# AUDIO_CODEC_CS4270.net
KiCad netlist of a schematic drawn in Altium Designer
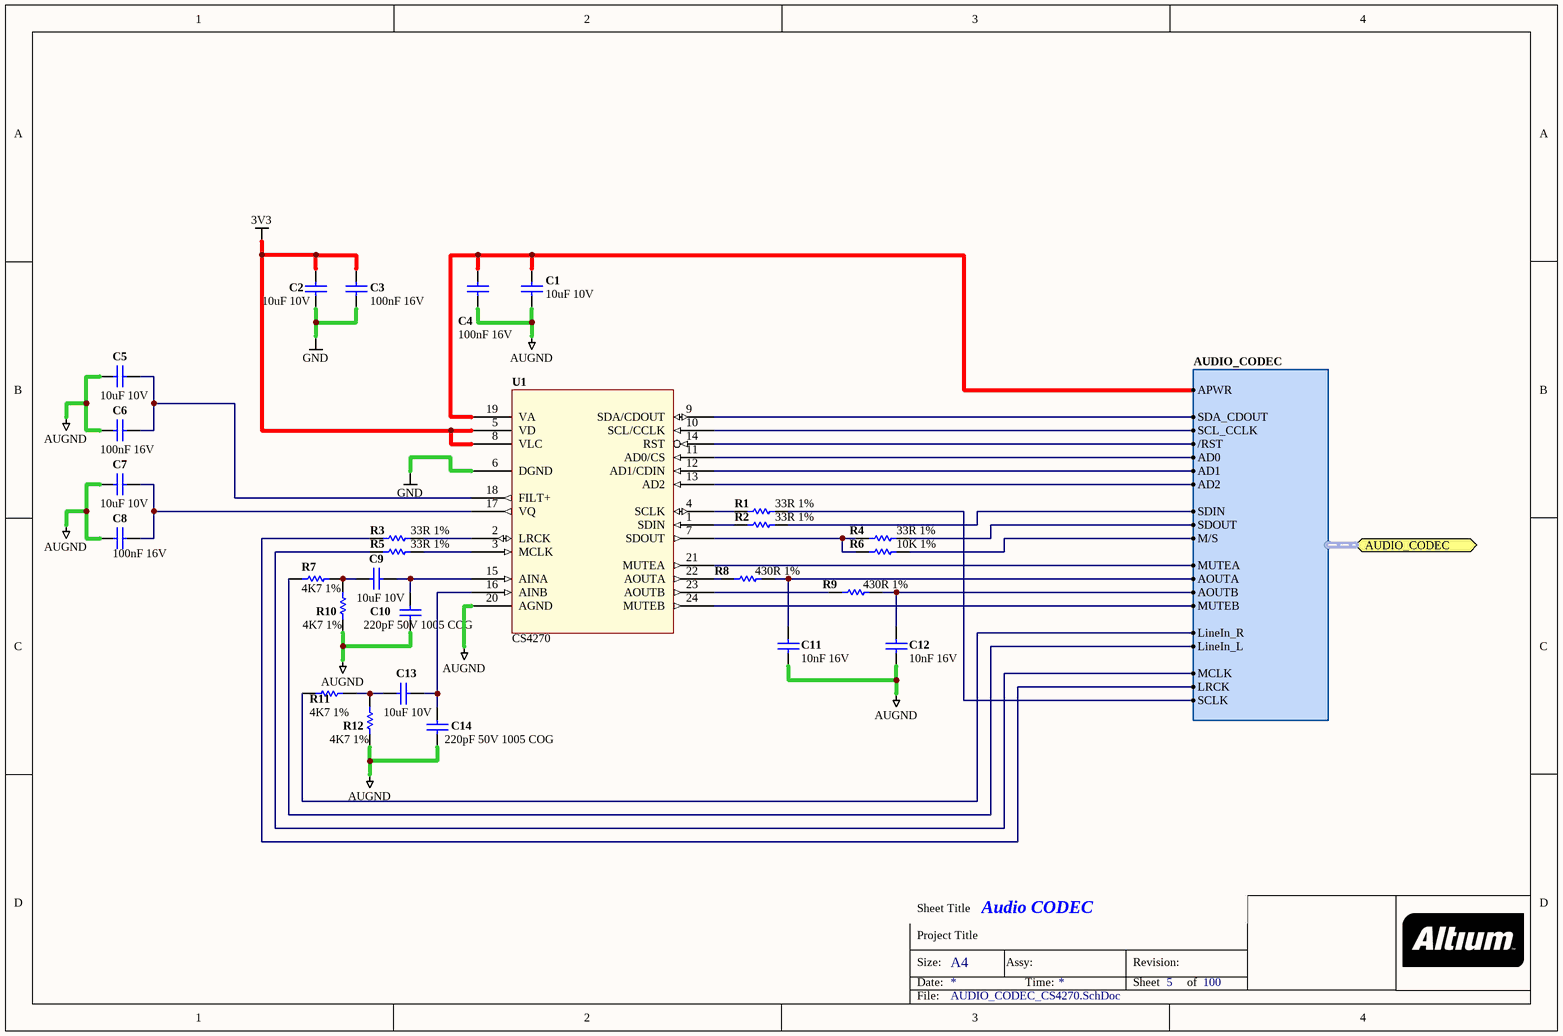
[diagram p0: AUDIO_CODEC_CS4270.SchDoc]

(export (version "E")
  (design (tool "Eeschema 10.0.6"))
  (components
    (comp (ref "C1")
      (value "10uF 10V")
      (footprint "CAPC2012-STAR")
      (description "Capacitor, Ceramic, 10uF 10% 10V 0805 (2012) X5R")
      (fields (field (name "TOLERANCE") "10 %"))
      (libsource (lib "AltiumDesignLibrary") (part "CAP-NP"))
    )
    (comp (ref "C2")
      (value "10uF 10V")
      (footprint "CAPC2012-STAR")
      (description "Capacitor, Ceramic, 10uF 10% 10V 0805 (2012) X5R")
      (fields (field (name "TOLERANCE") "10 %"))
      (libsource (lib "AltiumDesignLibrary") (part "CAP-NP"))
    )
    (comp (ref "C3")
      (value "100nF 16V")
      (footprint "CAPC1005-STAR")
      (description "Capacitor, Ceramic, 100nF 10% 16V 0402 (1005) X7R")
      (fields (field (name "TOLERANCE") "10 %"))
      (libsource (lib "AltiumDesignLibrary") (part "CAP-NP"))
    )
    (comp (ref "C4")
      (value "100nF 16V")
      (footprint "CAPC1005-STAR")
      (description "Capacitor, Ceramic, 100nF 10% 16V 0402 (1005) X7R")
      (fields (field (name "TOLERANCE") "10 %"))
      (libsource (lib "AltiumDesignLibrary") (part "CAP-NP"))
    )
    (comp (ref "C5")
      (value "10uF 10V")
      (footprint "CAPC2012-STAR")
      (description "Capacitor, Ceramic, 10uF 10% 10V 0805 (2012) X5R")
      (fields (field (name "TOLERANCE") "10 %"))
      (libsource (lib "AltiumDesignLibrary") (part "CAP-NP"))
    )
    (comp (ref "C6")
      (value "100nF 16V")
      (footprint "CAPC1005-STAR")
      (description "Capacitor, Ceramic, 100nF 10% 16V 0402 (1005) X7R")
      (fields (field (name "TOLERANCE") "10 %"))
      (libsource (lib "AltiumDesignLibrary") (part "CAP-NP"))
    )
    (comp (ref "C7")
      (value "10uF 10V")
      (footprint "CAPC2012-STAR")
      (description "Capacitor, Ceramic, 10uF 10% 10V 0805 (2012) X5R")
      (fields (field (name "TOLERANCE") "10 %"))
      (libsource (lib "AltiumDesignLibrary") (part "CAP-NP"))
    )
    (comp (ref "C8")
      (value "100nF 16V")
      (footprint "CAPC1005-STAR")
      (description "Capacitor, Ceramic, 100nF 10% 16V 0402 (1005) X7R")
      (fields (field (name "TOLERANCE") "10 %"))
      (libsource (lib "AltiumDesignLibrary") (part "CAP-NP"))
    )
    (comp (ref "C9")
      (value "10uF 10V")
      (footprint "CAPC2012-STAR")
      (description "Capacitor, Ceramic, 10uF 10% 10V 0805 (2012) X5R")
      (fields (field (name "TOLERANCE") "10 %"))
      (libsource (lib "AltiumDesignLibrary") (part "CAP-NP"))
    )
    (comp (ref "C10")
      (value "220pF 50V 1005 COG")
      (footprint "CAPC1005-STAR")
      (description "Capacitor, Ceramic, 220pF 5% 50V 0402 (1005) COG")
      (fields (field (name "TOLERANCE") "5 %"))
      (libsource (lib "AltiumDesignLibrary") (part "CAP-NP"))
    )
    (comp (ref "C11")
      (value "10nF 16V")
      (footprint "CAPC1005-STAR")
      (description "Capacitor, Ceramic, 10nF 10% 16V 0402 (1005) X7R")
      (fields (field (name "TOLERANCE") "10 %"))
      (libsource (lib "AltiumDesignLibrary") (part "CAP-NP"))
    )
    (comp (ref "C12")
      (value "10nF 16V")
      (footprint "CAPC1005-STAR")
      (description "Capacitor, Ceramic, 10nF 10% 16V 0402 (1005) X7R")
      (fields (field (name "TOLERANCE") "10 %"))
      (libsource (lib "AltiumDesignLibrary") (part "CAP-NP"))
    )
    (comp (ref "C13")
      (value "10uF 10V")
      (footprint "CAPC2012-STAR")
      (description "Capacitor, Ceramic, 10uF 10% 10V 0805 (2012) X5R")
      (fields (field (name "TOLERANCE") "10 %"))
      (libsource (lib "AltiumDesignLibrary") (part "CAP-NP"))
    )
    (comp (ref "C14")
      (value "220pF 50V 1005 COG")
      (footprint "CAPC1005-STAR")
      (description "Capacitor, Ceramic, 220pF 5% 50V 0402 (1005) COG")
      (fields (field (name "TOLERANCE") "5 %"))
      (libsource (lib "AltiumDesignLibrary") (part "CAP-NP"))
    )
    (comp (ref "R1")
      (value "33R 1%")
      (footprint "RESC1005-STAR")
      (description "Resistor, 33R 1% 0402 (1005)")
      (fields (field (name "TOLERANCE") "1 %"))
      (libsource (lib "AltiumDesignLibrary") (part "RES"))
    )
    (comp (ref "R2")
      (value "33R 1%")
      (footprint "RESC1005-STAR")
      (description "Resistor, 33R 1% 0402 (1005)")
      (fields (field (name "TOLERANCE") "1 %"))
      (libsource (lib "AltiumDesignLibrary") (part "RES"))
    )
    (comp (ref "R3")
      (value "33R 1%")
      (footprint "RESC1005-STAR")
      (description "Resistor, 33R 1% 0402 (1005)")
      (fields (field (name "TOLERANCE") "1 %"))
      (libsource (lib "AltiumDesignLibrary") (part "RES"))
    )
    (comp (ref "R4")
      (value "33R 1%")
      (footprint "RESC1005-STAR")
      (description "Resistor, 33R 1% 0402 (1005)")
      (fields (field (name "TOLERANCE") "1 %"))
      (libsource (lib "AltiumDesignLibrary") (part "RES"))
    )
    (comp (ref "R5")
      (value "33R 1%")
      (footprint "RESC1005-STAR")
      (description "Resistor, 33R 1% 0402 (1005)")
      (fields (field (name "TOLERANCE") "1 %"))
      (libsource (lib "AltiumDesignLibrary") (part "RES"))
    )
    (comp (ref "R6")
      (value "10K 1%")
      (footprint "RESC1005-STAR")
      (description "Resistor, 10K 1% 0402 (1005)")
      (fields (field (name "TOLERANCE") "1 %"))
      (libsource (lib "AltiumDesignLibrary") (part "RES"))
    )
    (comp (ref "R7")
      (value "4K7 1%")
      (footprint "RESC1005-STAR")
      (description "Resistor, 4K7 1% 0402 (1005)")
      (fields (field (name "TOLERANCE") "1 %"))
      (libsource (lib "AltiumDesignLibrary") (part "RES"))
    )
    (comp (ref "R8")
      (value "430R 1%")
      (footprint "RESC1005-STAR")
      (description "Resistor, 430R 1% 0402 (1005)")
      (fields (field (name "TOLERANCE") "1 %"))
      (libsource (lib "AltiumDesignLibrary") (part "RES"))
    )
    (comp (ref "R9")
      (value "430R 1%")
      (footprint "RESC1005-STAR")
      (description "Resistor, 430R 1% 0402 (1005)")
      (fields (field (name "TOLERANCE") "1 %"))
      (libsource (lib "AltiumDesignLibrary") (part "RES"))
    )
    (comp (ref "R10")
      (value "4K7 1%")
      (footprint "RESC1005-STAR")
      (description "Resistor, 4K7 1% 0402 (1005)")
      (fields (field (name "TOLERANCE") "1 %"))
      (libsource (lib "AltiumDesignLibrary") (part "RES"))
    )
    (comp (ref "R11")
      (value "4K7 1%")
      (footprint "RESC1005-STAR")
      (description "Resistor, 4K7 1% 0402 (1005)")
      (fields (field (name "TOLERANCE") "1 %"))
      (libsource (lib "AltiumDesignLibrary") (part "RES"))
    )
    (comp (ref "R12")
      (value "4K7 1%")
      (footprint "RESC1005-STAR")
      (description "Resistor, 4K7 1% 0402 (1005)")
      (fields (field (name "TOLERANCE") "1 %"))
      (libsource (lib "AltiumDesignLibrary") (part "RES"))
    )
    (comp (ref "U1")
      (value "CS4270")
      (footprint "TSSOP-24")
      (description "CS4270; 24-Bit, 192 kHz Stereo Audio CODEC")
      (libsource (lib "AltiumDesignLibrary") (part "CS4270"))
    )
  )
  (nets
    (net (code "3") (name "3V3") (class "Default")
      (node (ref "C2") (pin "1") (pinfunction "1_1") (pintype "passive"))
      (node (ref "C3") (pin "1") (pinfunction "1_1") (pintype "passive"))
      (node (ref "U1") (pin "5") (pinfunction "VD_5") (pintype "power_in"))
      (node (ref "U1") (pin "8") (pinfunction "VLC_8") (pintype "power_in"))
    )
    (net (code "4") (name "AUGND") (class "Default")
      (node (ref "C1") (pin "2") (pinfunction "2_2") (pintype "passive"))
      (node (ref "C10") (pin "2") (pinfunction "2_2") (pintype "passive"))
      (node (ref "C11") (pin "2") (pinfunction "2_2") (pintype "passive"))
      (node (ref "C12") (pin "2") (pinfunction "2_2") (pintype "passive"))
      (node (ref "C14") (pin "2") (pinfunction "2_2") (pintype "passive"))
      (node (ref "C4") (pin "2") (pinfunction "2_2") (pintype "passive"))
      (node (ref "C5") (pin "2") (pinfunction "2_2") (pintype "passive"))
      (node (ref "C6") (pin "1") (pinfunction "1_1") (pintype "passive"))
      (node (ref "C7") (pin "2") (pinfunction "2_2") (pintype "passive"))
      (node (ref "C8") (pin "2") (pinfunction "2_2") (pintype "passive"))
      (node (ref "R10") (pin "1") (pinfunction "1_1") (pintype "passive"))
      (node (ref "R12") (pin "1") (pinfunction "1_1") (pintype "passive"))
      (node (ref "U1") (pin "20") (pinfunction "AGND_20") (pintype "power_in"))
    )
    (net (code "5") (name "GND") (class "Default")
      (node (ref "C2") (pin "2") (pinfunction "2_2") (pintype "passive"))
      (node (ref "C3") (pin "2") (pinfunction "2_2") (pintype "passive"))
      (node (ref "U1") (pin "6") (pinfunction "DGND_6") (pintype "power_in"))
    )
    (net (code "6") (name "Net-(C9-Pad2)") (class "Default")
      (node (ref "C9") (pin "2") (pinfunction "2_2") (pintype "passive"))
      (node (ref "R10") (pin "2") (pinfunction "2_2") (pintype "passive"))
      (node (ref "R7") (pin "2") (pinfunction "2_2") (pintype "passive"))
    )
    (net (code "7") (name "Net-(C11-Pad1)") (class "Default")
      (node (ref "C11") (pin "1") (pinfunction "1_1") (pintype "passive"))
      (node (ref "R8") (pin "1") (pinfunction "1_1") (pintype "passive"))
    )
    (net (code "8") (name "Net-(C12-Pad1)") (class "Default")
      (node (ref "C12") (pin "1") (pinfunction "1_1") (pintype "passive"))
      (node (ref "R9") (pin "1") (pinfunction "1_1") (pintype "passive"))
    )
    (net (code "9") (name "Net-(C13-Pad2)") (class "Default")
      (node (ref "C13") (pin "2") (pinfunction "2_2") (pintype "passive"))
      (node (ref "R11") (pin "2") (pinfunction "2_2") (pintype "passive"))
      (node (ref "R12") (pin "2") (pinfunction "2_2") (pintype "passive"))
    )
    (net (code "10") (name "Net-(U1-AINA)") (class "Default")
      (node (ref "C10") (pin "1") (pinfunction "1_1") (pintype "passive"))
      (node (ref "C9") (pin "1") (pinfunction "1_1") (pintype "passive"))
      (node (ref "U1") (pin "15") (pinfunction "AINA_15") (pintype "input"))
    )
    (net (code "11") (name "Net-(U1-AINB)") (class "Default")
      (node (ref "C13") (pin "1") (pinfunction "1_1") (pintype "passive"))
      (node (ref "C14") (pin "1") (pinfunction "1_1") (pintype "passive"))
      (node (ref "U1") (pin "16") (pinfunction "AINB_16") (pintype "input"))
    )
    (net (code "12") (name "Net-(U1-AOUTA)") (class "Default")
      (node (ref "R8") (pin "2") (pinfunction "2_2") (pintype "passive"))
      (node (ref "U1") (pin "22") (pinfunction "AOUTA_22") (pintype "output"))
    )
    (net (code "13") (name "Net-(U1-AOUTB)") (class "Default")
      (node (ref "R9") (pin "2") (pinfunction "2_2") (pintype "passive"))
      (node (ref "U1") (pin "23") (pinfunction "AOUTB_23") (pintype "output"))
    )
    (net (code "14") (name "Net-(U1-FILT+)") (class "Default")
      (node (ref "C5") (pin "1") (pinfunction "1_1") (pintype "passive"))
      (node (ref "C6") (pin "2") (pinfunction "2_2") (pintype "passive"))
      (node (ref "U1") (pin "18") (pinfunction "FILT+_18") (pintype "output"))
    )
    (net (code "15") (name "Net-(U1-LRCK)") (class "Default")
      (node (ref "R3") (pin "2") (pinfunction "2_2") (pintype "passive"))
      (node (ref "U1") (pin "2") (pinfunction "LRCK_2") (pintype "bidirectional"))
    )
    (net (code "16") (name "Net-(U1-MCLK)") (class "Default")
      (node (ref "R5") (pin "2") (pinfunction "2_2") (pintype "passive"))
      (node (ref "U1") (pin "3") (pinfunction "MCLK_3") (pintype "input"))
    )
    (net (code "17") (name "Net-(U1-SCLK)") (class "Default")
      (node (ref "R1") (pin "1") (pinfunction "1_1") (pintype "passive"))
      (node (ref "U1") (pin "4") (pinfunction "SCLK_4") (pintype "bidirectional"))
    )
    (net (code "18") (name "Net-(U1-SDIN)") (class "Default")
      (node (ref "R2") (pin "1") (pinfunction "1_1") (pintype "passive"))
      (node (ref "U1") (pin "1") (pinfunction "SDIN_1") (pintype "input"))
    )
    (net (code "19") (name "Net-(U1-SDOUT)") (class "Default")
      (node (ref "R4") (pin "1") (pinfunction "1_1") (pintype "passive"))
      (node (ref "R6") (pin "2") (pinfunction "2_2") (pintype "passive"))
      (node (ref "U1") (pin "7") (pinfunction "SDOUT_7") (pintype "output"))
    )
    (net (code "20") (name "Net-(U1-VA)") (class "Default")
      (node (ref "C1") (pin "1") (pinfunction "1_1") (pintype "passive"))
      (node (ref "C4") (pin "1") (pinfunction "1_1") (pintype "passive"))
      (node (ref "U1") (pin "19") (pinfunction "VA_19") (pintype "power_in"))
    )
    (net (code "21") (name "Net-(U1-VQ)") (class "Default")
      (node (ref "C7") (pin "1") (pinfunction "1_1") (pintype "passive"))
      (node (ref "C8") (pin "1") (pinfunction "1_1") (pintype "passive"))
      (node (ref "U1") (pin "17") (pinfunction "VQ_17") (pintype "output"))
    )
    (net (code "22") (name "unconnected-(R1-Pad2)") (class "Default")
      (node (ref "R1") (pin "2") (pinfunction "2_2") (pintype "passive"))
    )
    (net (code "23") (name "unconnected-(R2-Pad2)") (class "Default")
      (node (ref "R2") (pin "2") (pinfunction "2_2") (pintype "passive"))
    )
    (net (code "24") (name "unconnected-(R3-Pad1)") (class "Default")
      (node (ref "R3") (pin "1") (pinfunction "1_1") (pintype "passive"))
    )
    (net (code "25") (name "unconnected-(R4-Pad2)") (class "Default")
      (node (ref "R4") (pin "2") (pinfunction "2_2") (pintype "passive"))
    )
    (net (code "26") (name "unconnected-(R5-Pad1)") (class "Default")
      (node (ref "R5") (pin "1") (pinfunction "1_1") (pintype "passive"))
    )
    (net (code "27") (name "unconnected-(R6-Pad1)") (class "Default")
      (node (ref "R6") (pin "1") (pinfunction "1_1") (pintype "passive"))
    )
    (net (code "28") (name "unconnected-(R7-Pad1)") (class "Default")
      (node (ref "R7") (pin "1") (pinfunction "1_1") (pintype "passive"))
    )
    (net (code "29") (name "unconnected-(R11-Pad1)") (class "Default")
      (node (ref "R11") (pin "1") (pinfunction "1_1") (pintype "passive"))
    )
    (net (code "30") (name "unconnected-(U1-AD0{slash}CS-Pad11)") (class "Default")
      (node (ref "U1") (pin "11") (pinfunction "AD0/CS_11") (pintype "input"))
    )
    (net (code "31") (name "unconnected-(U1-AD1{slash}CDIN-Pad12)") (class "Default")
      (node (ref "U1") (pin "12") (pinfunction "AD1/CDIN_12") (pintype "input"))
    )
    (net (code "32") (name "unconnected-(U1-AD2-Pad13)") (class "Default")
      (node (ref "U1") (pin "13") (pinfunction "AD2_13") (pintype "input"))
    )
    (net (code "33") (name "unconnected-(U1-MUTEA-Pad21)") (class "Default")
      (node (ref "U1") (pin "21") (pinfunction "MUTEA_21") (pintype "output"))
    )
    (net (code "34") (name "unconnected-(U1-MUTEB-Pad24)") (class "Default")
      (node (ref "U1") (pin "24") (pinfunction "MUTEB_24") (pintype "output"))
    )
    (net (code "35") (name "unconnected-(U1-RST-Pad14)") (class "Default")
      (node (ref "U1") (pin "14") (pinfunction "RST_14") (pintype "input"))
    )
    (net (code "36") (name "unconnected-(U1-SCL{slash}CCLK-Pad10)") (class "Default")
      (node (ref "U1") (pin "10") (pinfunction "SCL/CCLK_10") (pintype "input"))
    )
    (net (code "37") (name "unconnected-(U1-SDA{slash}CDOUT-Pad9)") (class "Default")
      (node (ref "U1") (pin "9") (pinfunction "SDA/CDOUT_9") (pintype "bidirectional"))
    )
  )
)
